# BEP3_Test_Interface3.net
KiCad netlist of a schematic drawn in EAGLE
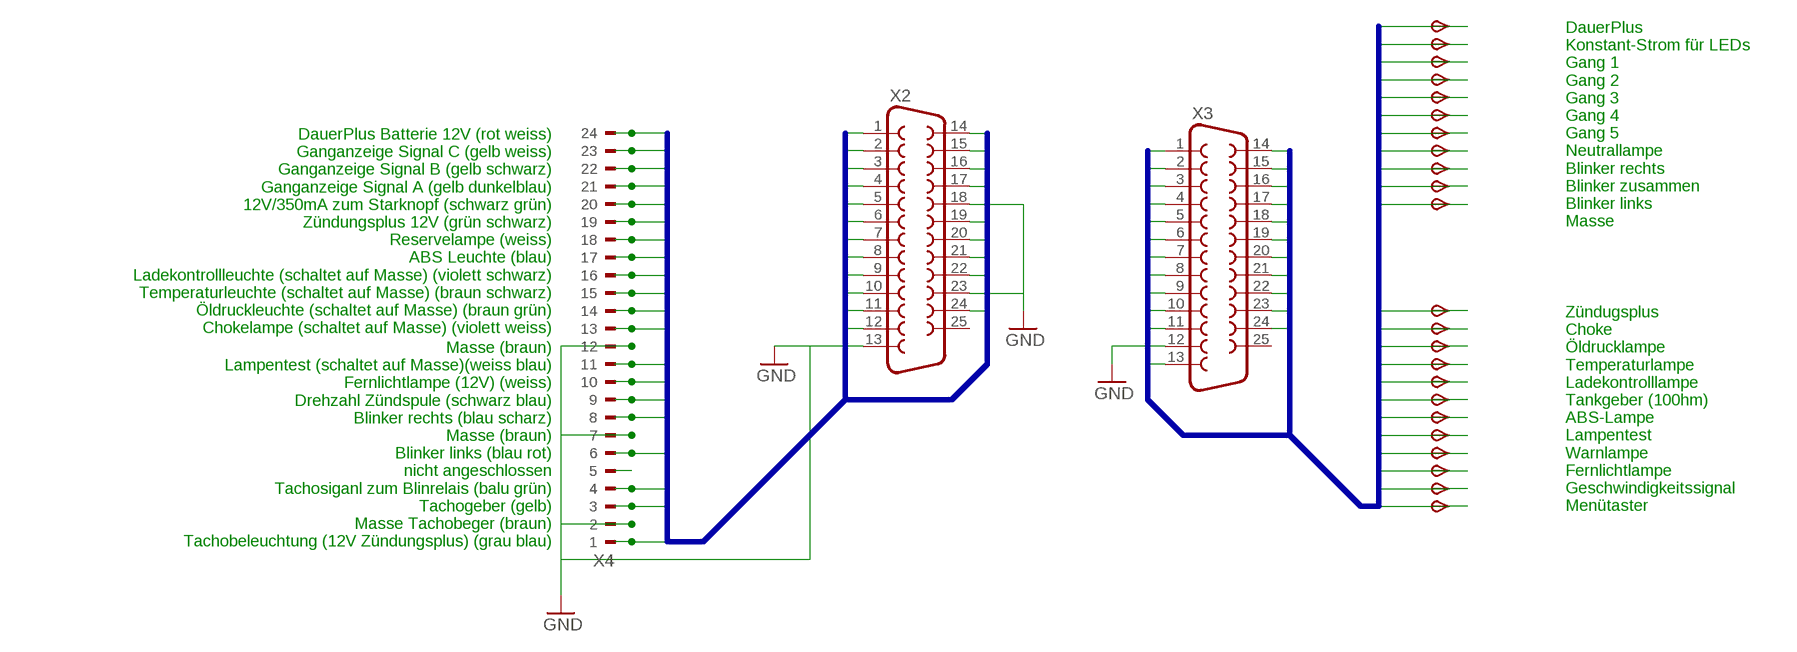
[diagram p0: schematic, sheet 1]
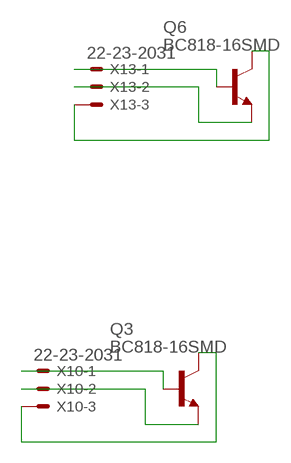
[diagram p1: schematic, sheet 2]
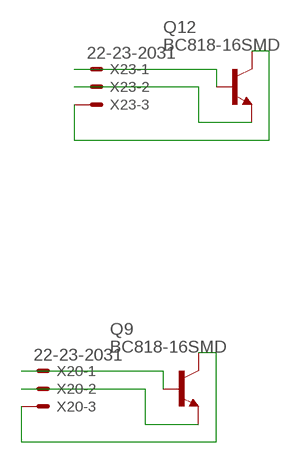
[diagram p2: schematic, sheet 3]
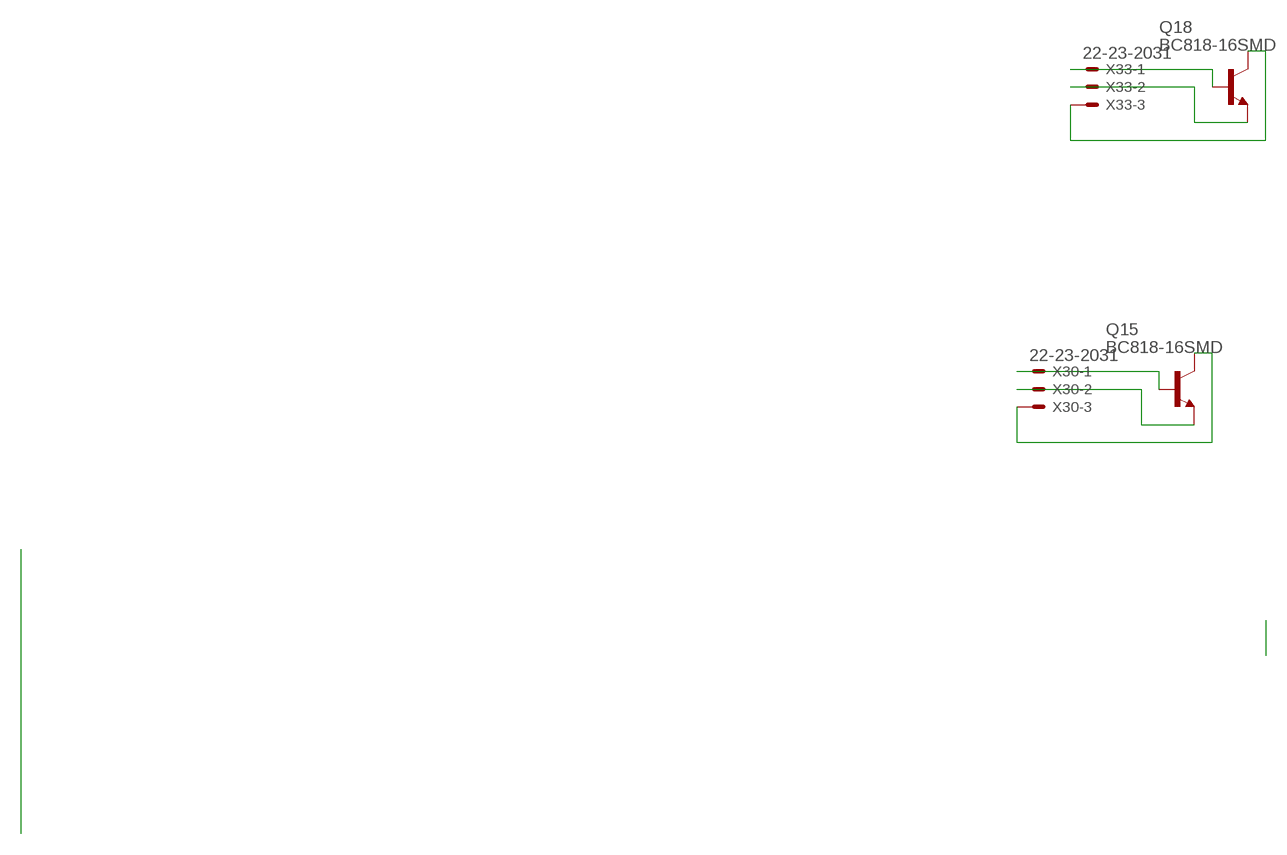
[diagram p3: schematic, sheet 4]
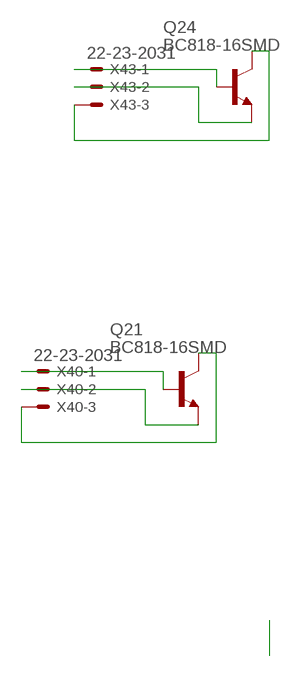
[diagram p4: schematic, sheet 5]

(export (version "E")
  (design (tool "Eeschema 10.0.6"))
  (components
    (comp (ref "TP1")
      (value "TPSFEDERPIN")
      (footprint "eagle-import:1,36ID")
      (libsource (lib "eagle-import") (part "TPSFEDERPIN"))
    )
    (comp (ref "TP2")
      (value "TPSFEDERPIN")
      (footprint "eagle-import:1,36ID")
      (libsource (lib "eagle-import") (part "TPSFEDERPIN"))
    )
    (comp (ref "TP3")
      (value "TPSFEDERPIN")
      (footprint "eagle-import:1,36ID")
      (libsource (lib "eagle-import") (part "TPSFEDERPIN"))
    )
    (comp (ref "TP4")
      (value "TPSFEDERPIN")
      (footprint "eagle-import:1,36ID")
      (libsource (lib "eagle-import") (part "TPSFEDERPIN"))
    )
    (comp (ref "TP5")
      (value "TPSFEDERPIN")
      (footprint "eagle-import:1,36ID")
      (libsource (lib "eagle-import") (part "TPSFEDERPIN"))
    )
    (comp (ref "TP6")
      (value "TPSFEDERPIN")
      (footprint "eagle-import:1,36ID")
      (libsource (lib "eagle-import") (part "TPSFEDERPIN"))
    )
    (comp (ref "TP7")
      (value "TPSFEDERPIN")
      (footprint "eagle-import:1,36ID")
      (libsource (lib "eagle-import") (part "TPSFEDERPIN"))
    )
    (comp (ref "TP8")
      (value "TPSFEDERPIN")
      (footprint "eagle-import:1,36ID")
      (libsource (lib "eagle-import") (part "TPSFEDERPIN"))
    )
    (comp (ref "TP9")
      (value "TPSFEDERPIN")
      (footprint "eagle-import:1,36ID")
      (libsource (lib "eagle-import") (part "TPSFEDERPIN"))
    )
    (comp (ref "TP10")
      (value "TPSFEDERPIN")
      (footprint "eagle-import:1,36ID")
      (libsource (lib "eagle-import") (part "TPSFEDERPIN"))
    )
    (comp (ref "TP11")
      (value "TPSFEDERPIN")
      (footprint "eagle-import:1,36ID")
      (libsource (lib "eagle-import") (part "TPSFEDERPIN"))
    )
    (comp (ref "TP12")
      (value "TPSFEDERPIN")
      (footprint "eagle-import:1,36ID")
      (libsource (lib "eagle-import") (part "TPSFEDERPIN"))
    )
    (comp (ref "TP13")
      (value "TPSFEDERPIN")
      (footprint "eagle-import:1,36ID")
      (libsource (lib "eagle-import") (part "TPSFEDERPIN"))
    )
    (comp (ref "TP16")
      (value "TPSFEDERPIN")
      (footprint "eagle-import:1,36ID")
      (libsource (lib "eagle-import") (part "TPSFEDERPIN"))
    )
    (comp (ref "TP17")
      (value "TPSFEDERPIN")
      (footprint "eagle-import:1,36ID")
      (libsource (lib "eagle-import") (part "TPSFEDERPIN"))
    )
    (comp (ref "TP18")
      (value "TPSFEDERPIN")
      (footprint "eagle-import:1,36ID")
      (libsource (lib "eagle-import") (part "TPSFEDERPIN"))
    )
    (comp (ref "TP19")
      (value "TPSFEDERPIN")
      (footprint "eagle-import:1,36ID")
      (libsource (lib "eagle-import") (part "TPSFEDERPIN"))
    )
    (comp (ref "TP21")
      (value "TPSFEDERPIN")
      (footprint "eagle-import:1,36ID")
      (libsource (lib "eagle-import") (part "TPSFEDERPIN"))
    )
    (comp (ref "TP22")
      (value "TPSFEDERPIN")
      (footprint "eagle-import:1,36ID")
      (libsource (lib "eagle-import") (part "TPSFEDERPIN"))
    )
    (comp (ref "TP23")
      (value "TPSFEDERPIN")
      (footprint "eagle-import:1,36ID")
      (libsource (lib "eagle-import") (part "TPSFEDERPIN"))
    )
    (comp (ref "TP24")
      (value "TPSFEDERPIN")
      (footprint "eagle-import:1,36ID")
      (libsource (lib "eagle-import") (part "TPSFEDERPIN"))
    )
    (comp (ref "TP25")
      (value "TPSFEDERPIN")
      (footprint "eagle-import:1,36ID")
      (libsource (lib "eagle-import") (part "TPSFEDERPIN"))
    )
    (comp (ref "TP26")
      (value "TPSFEDERPIN")
      (footprint "eagle-import:1,36ID")
      (libsource (lib "eagle-import") (part "TPSFEDERPIN"))
    )
    (comp (ref "X2")
      (value "F25H")
      (footprint "eagle-import:F25H")
      (libsource (lib "eagle-import") (part "F25H"))
    )
    (comp (ref "X3")
      (value "F25H")
      (footprint "eagle-import:F25H")
      (libsource (lib "eagle-import") (part "F25H"))
    )
    (comp (ref "X4")
      (value "CON_BMWTESTPINS")
      (footprint "eagle-import:24-TESTPIN_1,36ID")
      (libsource (lib "eagle-import") (part "CON_BMWTESTPINS"))
    )
    (comp (ref "Q9")
      (value "BC818-16SMD")
      (footprint "eagle-import:SOT23-BEC")
      (libsource (lib "eagle-import") (part "BC818SMD-16"))
    )
    (comp (ref "Q12")
      (value "BC818-16SMD")
      (footprint "eagle-import:SOT23-BEC")
      (libsource (lib "eagle-import") (part "BC818SMD-16"))
    )
    (comp (ref "X20")
      (value "22-23-2031")
      (footprint "eagle-import:22-23-2031")
      (fields (field (name "MF") "MOLEX"))
      (libsource (lib "eagle-import") (part "22-23-2031"))
    )
    (comp (ref "X23")
      (value "22-23-2031")
      (footprint "eagle-import:22-23-2031")
      (fields (field (name "MF") "MOLEX"))
      (libsource (lib "eagle-import") (part "22-23-2031"))
    )
    (comp (ref "Q3")
      (value "BC818-16SMD")
      (footprint "eagle-import:SOT23-BEC")
      (libsource (lib "eagle-import") (part "BC818SMD-16"))
    )
    (comp (ref "Q6")
      (value "BC818-16SMD")
      (footprint "eagle-import:SOT23-BEC")
      (libsource (lib "eagle-import") (part "BC818SMD-16"))
    )
    (comp (ref "X10")
      (value "22-23-2031")
      (footprint "eagle-import:22-23-2031")
      (fields (field (name "MF") "MOLEX"))
      (libsource (lib "eagle-import") (part "22-23-2031"))
    )
    (comp (ref "X13")
      (value "22-23-2031")
      (footprint "eagle-import:22-23-2031")
      (fields (field (name "MF") "MOLEX"))
      (libsource (lib "eagle-import") (part "22-23-2031"))
    )
    (comp (ref "Q21")
      (value "BC818-16SMD")
      (footprint "eagle-import:SOT23-BEC")
      (libsource (lib "eagle-import") (part "BC818SMD-16"))
    )
    (comp (ref "Q24")
      (value "BC818-16SMD")
      (footprint "eagle-import:SOT23-BEC")
      (libsource (lib "eagle-import") (part "BC818SMD-16"))
    )
    (comp (ref "X40")
      (value "22-23-2031")
      (footprint "eagle-import:22-23-2031")
      (fields (field (name "MF") "MOLEX"))
      (libsource (lib "eagle-import") (part "22-23-2031"))
    )
    (comp (ref "X43")
      (value "22-23-2031")
      (footprint "eagle-import:22-23-2031")
      (fields (field (name "MF") "MOLEX"))
      (libsource (lib "eagle-import") (part "22-23-2031"))
    )
    (comp (ref "Q15")
      (value "BC818-16SMD")
      (footprint "eagle-import:SOT23-BEC")
      (libsource (lib "eagle-import") (part "BC818SMD-16"))
    )
    (comp (ref "Q18")
      (value "BC818-16SMD")
      (footprint "eagle-import:SOT23-BEC")
      (libsource (lib "eagle-import") (part "BC818SMD-16"))
    )
    (comp (ref "X30")
      (value "22-23-2031")
      (footprint "eagle-import:22-23-2031")
      (fields (field (name "MF") "MOLEX"))
      (libsource (lib "eagle-import") (part "22-23-2031"))
    )
    (comp (ref "X33")
      (value "22-23-2031")
      (footprint "eagle-import:22-23-2031")
      (fields (field (name "MF") "MOLEX"))
      (libsource (lib "eagle-import") (part "22-23-2031"))
    )
  )
  (nets
    (net (code "1") (name "BMW1") (class "Default")
      (node (ref "X2") (pin "1") (pinfunction "1_1") (pintype "passive"))
      (node (ref "X4") (pin "P24") (pinfunction "24_P24") (pintype "passive"))
    )
    (net (code "2") (name "BMW2") (class "Default")
      (node (ref "X2") (pin "2") (pinfunction "2_2") (pintype "passive"))
      (node (ref "X4") (pin "P23") (pinfunction "23_P23") (pintype "passive"))
    )
    (net (code "3") (name "BMW3") (class "Default")
      (node (ref "X2") (pin "3") (pinfunction "3_3") (pintype "passive"))
      (node (ref "X4") (pin "P22") (pinfunction "22_P22") (pintype "passive"))
    )
    (net (code "4") (name "BMW4") (class "Default")
      (node (ref "X2") (pin "4") (pinfunction "4_4") (pintype "passive"))
      (node (ref "X4") (pin "P21") (pinfunction "21_P21") (pintype "passive"))
    )
    (net (code "5") (name "BMW5") (class "Default")
      (node (ref "X2") (pin "5") (pinfunction "5_5") (pintype "passive"))
      (node (ref "X4") (pin "P20") (pinfunction "20_P20") (pintype "passive"))
    )
    (net (code "6") (name "BMW6") (class "Default")
      (node (ref "X2") (pin "6") (pinfunction "6_6") (pintype "passive"))
      (node (ref "X4") (pin "P19") (pinfunction "19_P19") (pintype "passive"))
    )
    (net (code "7") (name "BMW7") (class "Default")
      (node (ref "X2") (pin "7") (pinfunction "7_7") (pintype "passive"))
      (node (ref "X4") (pin "P18") (pinfunction "18_P18") (pintype "passive"))
    )
    (net (code "8") (name "BMW8") (class "Default")
      (node (ref "X2") (pin "8") (pinfunction "8_8") (pintype "passive"))
      (node (ref "X4") (pin "P17") (pinfunction "17_P17") (pintype "passive"))
    )
    (net (code "9") (name "BMW9") (class "Default")
      (node (ref "X2") (pin "9") (pinfunction "9_9") (pintype "passive"))
      (node (ref "X4") (pin "P16") (pinfunction "16_P16") (pintype "passive"))
    )
    (net (code "10") (name "BMW10") (class "Default")
      (node (ref "X2") (pin "10") (pinfunction "10_10") (pintype "passive"))
      (node (ref "X4") (pin "P15") (pinfunction "15_P15") (pintype "passive"))
    )
    (net (code "11") (name "BMW11") (class "Default")
      (node (ref "X2") (pin "11") (pinfunction "11_11") (pintype "passive"))
      (node (ref "X4") (pin "P14") (pinfunction "14_P14") (pintype "passive"))
    )
    (net (code "12") (name "BMW12") (class "Default")
      (node (ref "X2") (pin "12") (pinfunction "12_12") (pintype "passive"))
      (node (ref "X4") (pin "P13") (pinfunction "13_P13") (pintype "passive"))
    )
    (net (code "13") (name "BMW14") (class "Default")
      (node (ref "X2") (pin "14") (pinfunction "14_14") (pintype "passive"))
      (node (ref "X4") (pin "P11") (pinfunction "11_P11") (pintype "passive"))
    )
    (net (code "14") (name "BMW15") (class "Default")
      (node (ref "X2") (pin "15") (pinfunction "15_15") (pintype "passive"))
      (node (ref "X4") (pin "P10") (pinfunction "10_P10") (pintype "passive"))
    )
    (net (code "15") (name "BMW16") (class "Default")
      (node (ref "X2") (pin "16") (pinfunction "16_16") (pintype "passive"))
      (node (ref "X4") (pin "P9") (pinfunction "9_P9") (pintype "passive"))
    )
    (net (code "16") (name "BMW17") (class "Default")
      (node (ref "X2") (pin "17") (pinfunction "17_17") (pintype "passive"))
      (node (ref "X4") (pin "P8") (pinfunction "8_P8") (pintype "passive"))
    )
    (net (code "17") (name "BMW19") (class "Default")
      (node (ref "X2") (pin "19") (pinfunction "19_19") (pintype "passive"))
      (node (ref "X4") (pin "P6") (pinfunction "6_P6") (pintype "passive"))
    )
    (net (code "18") (name "BMW21") (class "Default")
      (node (ref "X2") (pin "21") (pinfunction "21_21") (pintype "passive"))
      (node (ref "X4") (pin "P4") (pinfunction "4_P4") (pintype "passive"))
    )
    (net (code "19") (name "BMW22") (class "Default")
      (node (ref "X2") (pin "22") (pinfunction "22_22") (pintype "passive"))
      (node (ref "X4") (pin "P3") (pinfunction "3_P3") (pintype "passive"))
    )
    (net (code "20") (name "BMW24") (class "Default")
      (node (ref "X2") (pin "24") (pinfunction "24_24") (pintype "passive"))
      (node (ref "X4") (pin "P1") (pinfunction "1_P1") (pintype "passive"))
    )
    (net (code "21") (name "GND") (class "Default")
      (node (ref "X2") (pin "13") (pinfunction "13_13") (pintype "passive"))
      (node (ref "X2") (pin "18") (pinfunction "18_18") (pintype "passive"))
      (node (ref "X2") (pin "23") (pinfunction "23_23") (pintype "passive"))
      (node (ref "X3") (pin "12") (pinfunction "12_12") (pintype "passive"))
      (node (ref "X4") (pin "P12") (pinfunction "12_P12") (pintype "passive"))
      (node (ref "X4") (pin "P2") (pinfunction "2_P2") (pintype "passive"))
      (node (ref "X4") (pin "P7") (pinfunction "7_P7") (pintype "passive"))
    )
    (net (code "22") (name "Net-(X10A-S)") (class "Default")
      (node (ref "Q3") (pin "B") (pinfunction "B_B") (pintype "passive"))
      (node (ref "X10") (pin "1") (pinfunction "S_1") (pintype "passive"))
    )
    (net (code "23") (name "Net-(X10B-S)") (class "Default")
      (node (ref "Q3") (pin "E") (pinfunction "E_E") (pintype "passive"))
      (node (ref "X10") (pin "2") (pinfunction "S_2") (pintype "passive"))
    )
    (net (code "24") (name "Net-(X10C-S)") (class "Default")
      (node (ref "Q3") (pin "C") (pinfunction "C_C") (pintype "passive"))
      (node (ref "X10") (pin "3") (pinfunction "S_3") (pintype "passive"))
    )
    (net (code "25") (name "Net-(X13A-S)") (class "Default")
      (node (ref "Q6") (pin "B") (pinfunction "B_B") (pintype "passive"))
      (node (ref "X13") (pin "1") (pinfunction "S_1") (pintype "passive"))
    )
    (net (code "26") (name "Net-(X13B-S)") (class "Default")
      (node (ref "Q6") (pin "E") (pinfunction "E_E") (pintype "passive"))
      (node (ref "X13") (pin "2") (pinfunction "S_2") (pintype "passive"))
    )
    (net (code "27") (name "Net-(X13C-S)") (class "Default")
      (node (ref "Q6") (pin "C") (pinfunction "C_C") (pintype "passive"))
      (node (ref "X13") (pin "3") (pinfunction "S_3") (pintype "passive"))
    )
    (net (code "28") (name "Net-(X20A-S)") (class "Default")
      (node (ref "Q9") (pin "B") (pinfunction "B_B") (pintype "passive"))
      (node (ref "X20") (pin "1") (pinfunction "S_1") (pintype "passive"))
    )
    (net (code "29") (name "Net-(X20B-S)") (class "Default")
      (node (ref "Q9") (pin "E") (pinfunction "E_E") (pintype "passive"))
      (node (ref "X20") (pin "2") (pinfunction "S_2") (pintype "passive"))
    )
    (net (code "30") (name "Net-(X20C-S)") (class "Default")
      (node (ref "Q9") (pin "C") (pinfunction "C_C") (pintype "passive"))
      (node (ref "X20") (pin "3") (pinfunction "S_3") (pintype "passive"))
    )
    (net (code "31") (name "Net-(X23A-S)") (class "Default")
      (node (ref "Q12") (pin "B") (pinfunction "B_B") (pintype "passive"))
      (node (ref "X23") (pin "1") (pinfunction "S_1") (pintype "passive"))
    )
    (net (code "32") (name "Net-(X23B-S)") (class "Default")
      (node (ref "Q12") (pin "E") (pinfunction "E_E") (pintype "passive"))
      (node (ref "X23") (pin "2") (pinfunction "S_2") (pintype "passive"))
    )
    (net (code "33") (name "Net-(X23C-S)") (class "Default")
      (node (ref "Q12") (pin "C") (pinfunction "C_C") (pintype "passive"))
      (node (ref "X23") (pin "3") (pinfunction "S_3") (pintype "passive"))
    )
    (net (code "34") (name "Net-(X30A-S)") (class "Default")
      (node (ref "Q15") (pin "B") (pinfunction "B_B") (pintype "passive"))
      (node (ref "X30") (pin "1") (pinfunction "S_1") (pintype "passive"))
    )
    (net (code "35") (name "Net-(X30B-S)") (class "Default")
      (node (ref "Q15") (pin "E") (pinfunction "E_E") (pintype "passive"))
      (node (ref "X30") (pin "2") (pinfunction "S_2") (pintype "passive"))
    )
    (net (code "36") (name "Net-(X30C-S)") (class "Default")
      (node (ref "Q15") (pin "C") (pinfunction "C_C") (pintype "passive"))
      (node (ref "X30") (pin "3") (pinfunction "S_3") (pintype "passive"))
    )
    (net (code "37") (name "Net-(X33A-S)") (class "Default")
      (node (ref "Q18") (pin "B") (pinfunction "B_B") (pintype "passive"))
      (node (ref "X33") (pin "1") (pinfunction "S_1") (pintype "passive"))
    )
    (net (code "38") (name "Net-(X33B-S)") (class "Default")
      (node (ref "Q18") (pin "E") (pinfunction "E_E") (pintype "passive"))
      (node (ref "X33") (pin "2") (pinfunction "S_2") (pintype "passive"))
    )
    (net (code "39") (name "Net-(X33C-S)") (class "Default")
      (node (ref "Q18") (pin "C") (pinfunction "C_C") (pintype "passive"))
      (node (ref "X33") (pin "3") (pinfunction "S_3") (pintype "passive"))
    )
    (net (code "40") (name "Net-(X40A-S)") (class "Default")
      (node (ref "Q21") (pin "B") (pinfunction "B_B") (pintype "passive"))
      (node (ref "X40") (pin "1") (pinfunction "S_1") (pintype "passive"))
    )
    (net (code "41") (name "Net-(X40B-S)") (class "Default")
      (node (ref "Q21") (pin "E") (pinfunction "E_E") (pintype "passive"))
      (node (ref "X40") (pin "2") (pinfunction "S_2") (pintype "passive"))
    )
    (net (code "42") (name "Net-(X40C-S)") (class "Default")
      (node (ref "Q21") (pin "C") (pinfunction "C_C") (pintype "passive"))
      (node (ref "X40") (pin "3") (pinfunction "S_3") (pintype "passive"))
    )
    (net (code "43") (name "Net-(X43A-S)") (class "Default")
      (node (ref "Q24") (pin "B") (pinfunction "B_B") (pintype "passive"))
      (node (ref "X43") (pin "1") (pinfunction "S_1") (pintype "passive"))
    )
    (net (code "44") (name "Net-(X43B-S)") (class "Default")
      (node (ref "Q24") (pin "E") (pinfunction "E_E") (pintype "passive"))
      (node (ref "X43") (pin "2") (pinfunction "S_2") (pintype "passive"))
    )
    (net (code "45") (name "Net-(X43C-S)") (class "Default")
      (node (ref "Q24") (pin "C") (pinfunction "C_C") (pintype "passive"))
      (node (ref "X43") (pin "3") (pinfunction "S_3") (pintype "passive"))
    )
    (net (code "46") (name "WAGO1") (class "Default")
      (node (ref "TP1") (pin "P$1") (pinfunction "PP_P$1") (pintype "input"))
      (node (ref "X3") (pin "1") (pinfunction "1_1") (pintype "passive"))
    )
    (net (code "47") (name "WAGO2") (class "Default")
      (node (ref "TP2") (pin "P$1") (pinfunction "PP_P$1") (pintype "input"))
      (node (ref "X3") (pin "2") (pinfunction "2_2") (pintype "passive"))
    )
    (net (code "48") (name "WAGO3") (class "Default")
      (node (ref "TP3") (pin "P$1") (pinfunction "PP_P$1") (pintype "input"))
      (node (ref "X3") (pin "3") (pinfunction "3_3") (pintype "passive"))
    )
    (net (code "49") (name "WAGO4") (class "Default")
      (node (ref "TP4") (pin "P$1") (pinfunction "PP_P$1") (pintype "input"))
      (node (ref "X3") (pin "4") (pinfunction "4_4") (pintype "passive"))
    )
    (net (code "50") (name "WAGO5") (class "Default")
      (node (ref "TP5") (pin "P$1") (pinfunction "PP_P$1") (pintype "input"))
      (node (ref "X3") (pin "5") (pinfunction "5_5") (pintype "passive"))
    )
    (net (code "51") (name "WAGO6") (class "Default")
      (node (ref "TP6") (pin "P$1") (pinfunction "PP_P$1") (pintype "input"))
      (node (ref "X3") (pin "6") (pinfunction "6_6") (pintype "passive"))
    )
    (net (code "52") (name "WAGO7") (class "Default")
      (node (ref "TP7") (pin "P$1") (pinfunction "PP_P$1") (pintype "input"))
      (node (ref "X3") (pin "7") (pinfunction "7_7") (pintype "passive"))
    )
    (net (code "53") (name "WAGO8") (class "Default")
      (node (ref "TP8") (pin "P$1") (pinfunction "PP_P$1") (pintype "input"))
      (node (ref "X3") (pin "8") (pinfunction "8_8") (pintype "passive"))
    )
    (net (code "54") (name "WAGO9") (class "Default")
      (node (ref "TP9") (pin "P$1") (pinfunction "PP_P$1") (pintype "input"))
      (node (ref "X3") (pin "9") (pinfunction "9_9") (pintype "passive"))
    )
    (net (code "55") (name "WAGO10") (class "Default")
      (node (ref "TP10") (pin "P$1") (pinfunction "PP_P$1") (pintype "input"))
      (node (ref "X3") (pin "10") (pinfunction "10_10") (pintype "passive"))
    )
    (net (code "56") (name "WAGO11") (class "Default")
      (node (ref "TP11") (pin "P$1") (pinfunction "PP_P$1") (pintype "input"))
      (node (ref "X3") (pin "11") (pinfunction "11_11") (pintype "passive"))
    )
    (net (code "57") (name "WAGO13") (class "Default")
      (node (ref "TP12") (pin "P$1") (pinfunction "PP_P$1") (pintype "input"))
      (node (ref "X3") (pin "13") (pinfunction "13_13") (pintype "passive"))
    )
    (net (code "58") (name "WAGO14") (class "Default")
      (node (ref "TP16") (pin "P$1") (pinfunction "PP_P$1") (pintype "input"))
      (node (ref "X3") (pin "14") (pinfunction "14_14") (pintype "passive"))
    )
    (net (code "59") (name "WAGO15") (class "Default")
      (node (ref "TP17") (pin "P$1") (pinfunction "PP_P$1") (pintype "input"))
      (node (ref "X3") (pin "15") (pinfunction "15_15") (pintype "passive"))
    )
    (net (code "60") (name "WAGO16") (class "Default")
      (node (ref "TP18") (pin "P$1") (pinfunction "PP_P$1") (pintype "input"))
      (node (ref "X3") (pin "16") (pinfunction "16_16") (pintype "passive"))
    )
    (net (code "61") (name "WAGO17") (class "Default")
      (node (ref "TP19") (pin "P$1") (pinfunction "PP_P$1") (pintype "input"))
      (node (ref "X3") (pin "17") (pinfunction "17_17") (pintype "passive"))
    )
    (net (code "62") (name "WAGO18") (class "Default")
      (node (ref "TP21") (pin "P$1") (pinfunction "PP_P$1") (pintype "input"))
      (node (ref "X3") (pin "18") (pinfunction "18_18") (pintype "passive"))
    )
    (net (code "63") (name "WAGO19") (class "Default")
      (node (ref "TP22") (pin "P$1") (pinfunction "PP_P$1") (pintype "input"))
      (node (ref "X3") (pin "19") (pinfunction "19_19") (pintype "passive"))
    )
    (net (code "64") (name "WAGO20") (class "Default")
      (node (ref "TP23") (pin "P$1") (pinfunction "PP_P$1") (pintype "input"))
      (node (ref "X3") (pin "20") (pinfunction "20_20") (pintype "passive"))
    )
    (net (code "65") (name "WAGO21") (class "Default")
      (node (ref "TP24") (pin "P$1") (pinfunction "PP_P$1") (pintype "input"))
      (node (ref "X3") (pin "21") (pinfunction "21_21") (pintype "passive"))
    )
    (net (code "66") (name "WAGO22") (class "Default")
      (node (ref "TP25") (pin "P$1") (pinfunction "PP_P$1") (pintype "input"))
      (node (ref "X3") (pin "22") (pinfunction "22_22") (pintype "passive"))
    )
    (net (code "67") (name "WAGO23") (class "Default")
      (node (ref "TP26") (pin "P$1") (pinfunction "PP_P$1") (pintype "input"))
      (node (ref "X3") (pin "23") (pinfunction "23_23") (pintype "passive"))
    )
    (net (code "68") (name "WAGO24") (class "Default")
      (node (ref "TP13") (pin "P$1") (pinfunction "PP_P$1") (pintype "input"))
      (node (ref "X3") (pin "24") (pinfunction "24_24") (pintype "passive"))
    )
    (net (code "69") (name "unconnected-(X2-Pad20)") (class "Default")
      (node (ref "X2") (pin "20") (pinfunction "20_20") (pintype "passive"))
    )
    (net (code "70") (name "unconnected-(X2-Pad25)") (class "Default")
      (node (ref "X2") (pin "25") (pinfunction "25_25") (pintype "passive"))
    )
    (net (code "71") (name "unconnected-(X3-Pad25)") (class "Default")
      (node (ref "X3") (pin "25") (pinfunction "25_25") (pintype "passive"))
    )
    (net (code "72") (name "unconnected-(X4-5-PadP5)") (class "Default")
      (node (ref "X4") (pin "P5") (pinfunction "5_P5") (pintype "passive"))
    )
  )
)
